# Schematic_WMR.net
KiCad netlist of a schematic drawn in Altium Designer
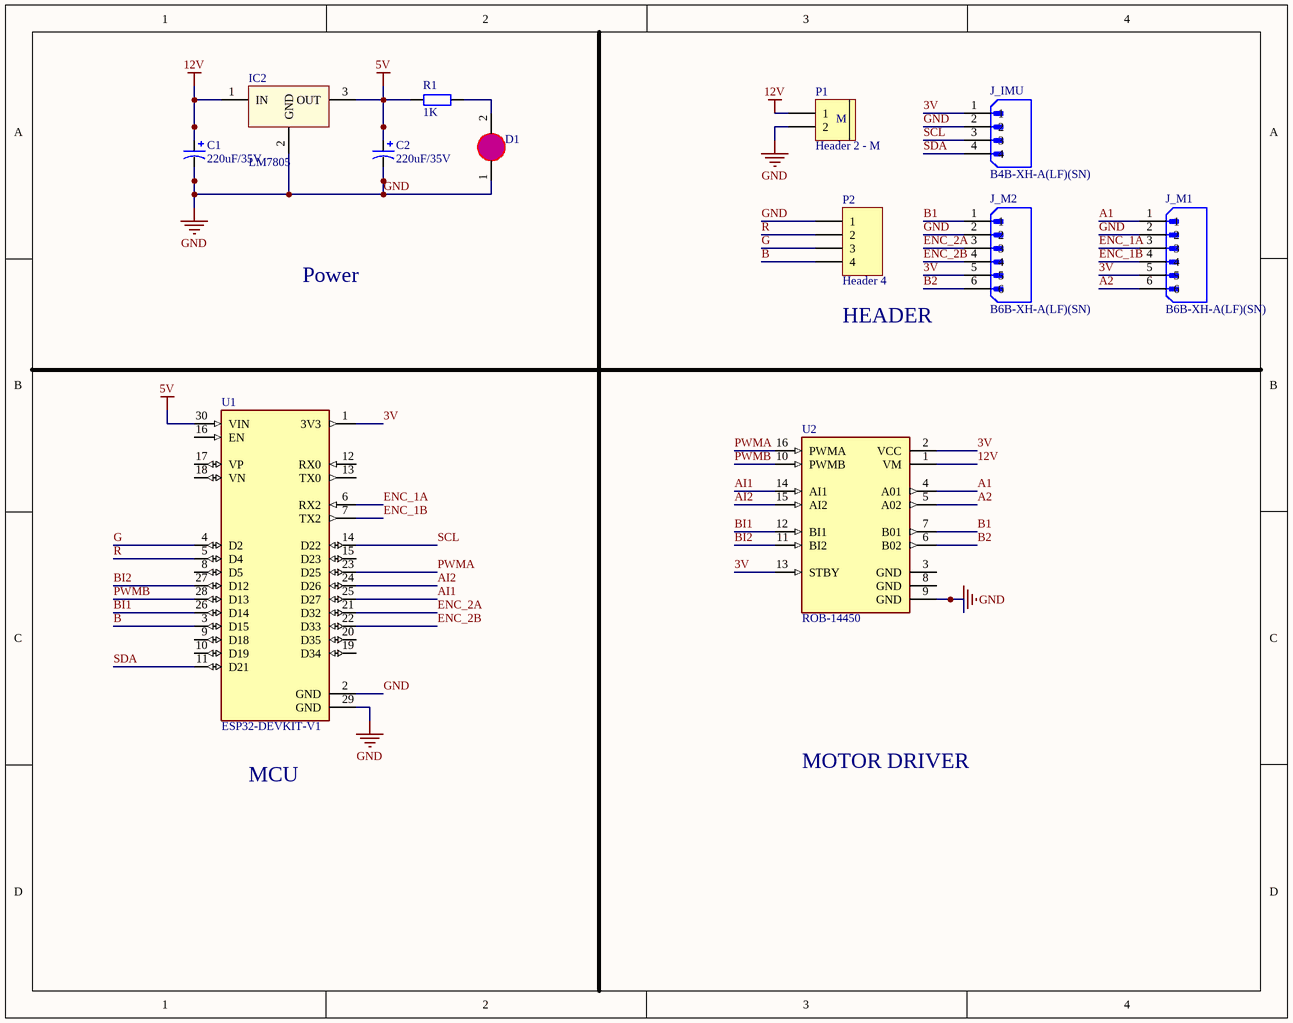
[diagram p0: Schematic_WMR.SchDoc]

(export (version "E")
  (design (tool "Eeschema 10.0.6"))
  (components
    (comp (ref "C1")
      (value "220uF/35V")
      (footprint "CAP_ALUM_SMD_80102_TYPE_F")
      (description "CAP ALUM 220uF 20% 35V SMD")
      (fields (field (name "MPN") "EEE-FK1V221P") (field (name "MFR") "Panasonic"))
      (libsource (lib "BYTECH_HW_LIB_2019 (1)") (part "EEE-FK1V221P"))
    )
    (comp (ref "C2")
      (value "220uF/35V")
      (footprint "CAP_ALUM_SMD_80102_TYPE_F")
      (description "CAP ALUM 220uF 20% 35V SMD")
      (fields (field (name "MPN") "EEE-FK1V221P") (field (name "MFR") "Panasonic"))
      (libsource (lib "BYTECH_HW_LIB_2019 (1)") (part "EEE-FK1V221P"))
    )
    (comp (ref "D1")
      (value "LED3")
      (footprint "LED0805")
      (description "LED SMD 0805")
      (libsource (lib "My Library") (part "LED0805"))
    )
    (comp (ref "IC2")
      (value "LM7805")
      (footprint "QTO-220")
      (description "On ap +, from + 5 to + 24VDC")
      (libsource (lib "My Library") (part "LM78xx"))
    )
    (comp (ref "J_IMU")
      (value "B4B-XH-A(LF)(SN)")
      (footprint "JST_B4B-XH-A(LF)(SN)")
      (description "Connector Header Through Hole 4 position 0.098 (2.50mm)")
      (fields (field (name "MF") "JST Sales"))
      (libsource (lib "B4B-XH-A_LF__SN_") (part "B4B-XH-A(LF)(SN)"))
    )
    (comp (ref "J_M1")
      (value "B6B-XH-A(LF)(SN)")
      (footprint "JST_B6B-XH-A(LF)(SN)")
      (description "Connector Header Through Hole 6 position 0.098 (2.50mm)")
      (fields (field (name "MF") "JST Sales"))
      (libsource (lib "B6B-XH-A_LF__SN_") (part "B6B-XH-A(LF)(SN)"))
    )
    (comp (ref "J_M2")
      (value "B6B-XH-A(LF)(SN)")
      (footprint "JST_B6B-XH-A(LF)(SN)")
      (description "Connector Header Through Hole 6 position 0.098 (2.50mm)")
      (fields (field (name "MF") "JST Sales"))
      (libsource (lib "B6B-XH-A_LF__SN_") (part "B6B-XH-A(LF)(SN)"))
    )
    (comp (ref "P1")
      (value "Header 2 - M")
      (footprint "Medium - Header 2")
      (description "Header, 2-Pin, Medium")
      (fields (field (name "PUBLISHER") "Altium Limited"))
      (libsource (lib "BYTECH_HW_LIB_2019 (1)") (part "Header 2 - M"))
    )
    (comp (ref "P2")
      (value "Header 4")
      (footprint "HDR1X4")
      (description "Header, 4-Pin")
      (fields (field (name "PUBLISHER") "Altium Limited"))
      (libsource (lib "My Library") (part "Header 4"))
    )
    (comp (ref "R1")
      (value "1K")
      (footprint "SM-0805")
      (description "Resistor SMD")
      (libsource (lib "My Library") (part "RM"))
    )
    (comp (ref "U1")
      (value "ESP32-DEVKIT-V1")
      (footprint "MODULE_ESP32_DEVKIT_V1")
      (fields (field (name "MF") "Do it"))
      (libsource (lib "ESP32-DEVKIT-V1") (part "ESP32-DEVKIT-V1"))
    )
    (comp (ref "U2")
      (value "ROB-14450")
      (footprint "MODULE_ROB-14450")
      (description "TB6612FNG Motor Controller/Driver Power Management Evaluation Board")
      (fields (field (name "MF") "SparkFun Electronics"))
      (libsource (lib "ROB-14450") (part "ROB-14450"))
    )
  )
  (nets
    (net (code "1") (name "/3V") (class "Default")
      (node (ref "J_IMU") (pin "1") (pinfunction "1_1") (pintype "passive"))
      (node (ref "J_M1") (pin "5") (pinfunction "5_5") (pintype "passive"))
      (node (ref "J_M2") (pin "5") (pinfunction "5_5") (pintype "passive"))
      (node (ref "U1") (pin "1") (pinfunction "3V3_1") (pintype "output"))
      (node (ref "U2") (pin "13") (pinfunction "STBY_13") (pintype "input"))
      (node (ref "U2") (pin "2") (pinfunction "VCC_2") (pintype "power_in"))
    )
    (net (code "2") (name "/A1") (class "Default")
      (node (ref "J_M1") (pin "1") (pinfunction "1_1") (pintype "passive"))
      (node (ref "U2") (pin "4") (pinfunction "A01_4") (pintype "output"))
    )
    (net (code "3") (name "/A2") (class "Default")
      (node (ref "J_M1") (pin "6") (pinfunction "6_6") (pintype "passive"))
      (node (ref "U2") (pin "5") (pinfunction "A02_5") (pintype "output"))
    )
    (net (code "4") (name "/AI1") (class "Default")
      (node (ref "U1") (pin "25") (pinfunction "D27_25") (pintype "bidirectional"))
      (node (ref "U2") (pin "14") (pinfunction "AI1_14") (pintype "input"))
    )
    (net (code "5") (name "/AI2") (class "Default")
      (node (ref "U1") (pin "24") (pinfunction "D26_24") (pintype "bidirectional"))
      (node (ref "U2") (pin "15") (pinfunction "AI2_15") (pintype "input"))
    )
    (net (code "6") (name "/B") (class "Default")
      (node (ref "P2") (pin "4") (pinfunction "4_4") (pintype "passive"))
      (node (ref "U1") (pin "3") (pinfunction "D15_3") (pintype "bidirectional"))
    )
    (net (code "7") (name "/B1") (class "Default")
      (node (ref "J_M2") (pin "1") (pinfunction "1_1") (pintype "passive"))
      (node (ref "U2") (pin "7") (pinfunction "B01_7") (pintype "output"))
    )
    (net (code "8") (name "/B2") (class "Default")
      (node (ref "J_M2") (pin "6") (pinfunction "6_6") (pintype "passive"))
      (node (ref "U2") (pin "6") (pinfunction "B02_6") (pintype "output"))
    )
    (net (code "9") (name "/BI1") (class "Default")
      (node (ref "U1") (pin "26") (pinfunction "D14_26") (pintype "bidirectional"))
      (node (ref "U2") (pin "12") (pinfunction "BI1_12") (pintype "input"))
    )
    (net (code "10") (name "/BI2") (class "Default")
      (node (ref "U1") (pin "27") (pinfunction "D12_27") (pintype "bidirectional"))
      (node (ref "U2") (pin "11") (pinfunction "BI2_11") (pintype "input"))
    )
    (net (code "11") (name "/ENC_1A") (class "Default")
      (node (ref "J_M1") (pin "3") (pinfunction "3_3") (pintype "passive"))
      (node (ref "U1") (pin "6") (pinfunction "RX2_6") (pintype "input"))
    )
    (net (code "12") (name "/ENC_1B") (class "Default")
      (node (ref "J_M1") (pin "4") (pinfunction "4_4") (pintype "passive"))
      (node (ref "U1") (pin "7") (pinfunction "TX2_7") (pintype "output"))
    )
    (net (code "13") (name "/ENC_2A") (class "Default")
      (node (ref "J_M2") (pin "3") (pinfunction "3_3") (pintype "passive"))
      (node (ref "U1") (pin "21") (pinfunction "D32_21") (pintype "bidirectional"))
    )
    (net (code "14") (name "/ENC_2B") (class "Default")
      (node (ref "J_M2") (pin "4") (pinfunction "4_4") (pintype "passive"))
      (node (ref "U1") (pin "22") (pinfunction "D33_22") (pintype "bidirectional"))
    )
    (net (code "15") (name "/G") (class "Default")
      (node (ref "P2") (pin "3") (pinfunction "3_3") (pintype "passive"))
      (node (ref "U1") (pin "4") (pinfunction "D2_4") (pintype "bidirectional"))
    )
    (net (code "16") (name "/PWMA") (class "Default")
      (node (ref "U1") (pin "23") (pinfunction "D25_23") (pintype "bidirectional"))
      (node (ref "U2") (pin "16") (pinfunction "PWMA_16") (pintype "input"))
    )
    (net (code "17") (name "/PWMB") (class "Default")
      (node (ref "U1") (pin "28") (pinfunction "D13_28") (pintype "bidirectional"))
      (node (ref "U2") (pin "10") (pinfunction "PWMB_10") (pintype "input"))
    )
    (net (code "18") (name "/R") (class "Default")
      (node (ref "P2") (pin "2") (pinfunction "2_2") (pintype "passive"))
      (node (ref "U1") (pin "5") (pinfunction "D4_5") (pintype "bidirectional"))
    )
    (net (code "19") (name "/SCL") (class "Default")
      (node (ref "J_IMU") (pin "3") (pinfunction "3_3") (pintype "passive"))
      (node (ref "U1") (pin "14") (pinfunction "D22_14") (pintype "bidirectional"))
    )
    (net (code "20") (name "/SDA") (class "Default")
      (node (ref "J_IMU") (pin "4") (pinfunction "4_4") (pintype "passive"))
      (node (ref "U1") (pin "11") (pinfunction "D21_11") (pintype "bidirectional"))
    )
    (net (code "21") (name "5V") (class "Default")
      (node (ref "C2") (pin "1") (pinfunction "1_1") (pintype "passive"))
      (node (ref "IC2") (pin "3") (pinfunction "OUT_3") (pintype "passive"))
      (node (ref "R1") (pin "1") (pinfunction "1_1") (pintype "passive"))
      (node (ref "U1") (pin "30") (pinfunction "VIN_30") (pintype "input"))
    )
    (net (code "22") (name "12V") (class "Default")
      (node (ref "C1") (pin "1") (pinfunction "1_1") (pintype "passive"))
      (node (ref "IC2") (pin "1") (pinfunction "IN_1") (pintype "passive"))
      (node (ref "P1") (pin "1") (pinfunction "1_1") (pintype "passive"))
      (node (ref "U2") (pin "1") (pinfunction "VM_1") (pintype "power_in"))
    )
    (net (code "23") (name "GND") (class "Default")
      (node (ref "C1") (pin "2") (pinfunction "2_2") (pintype "passive"))
      (node (ref "C2") (pin "2") (pinfunction "2_2") (pintype "passive"))
      (node (ref "D1") (pin "1") (pinfunction "A_1") (pintype "passive"))
      (node (ref "IC2") (pin "2") (pinfunction "GND_2") (pintype "passive"))
      (node (ref "J_IMU") (pin "2") (pinfunction "2_2") (pintype "passive"))
      (node (ref "J_M1") (pin "2") (pinfunction "2_2") (pintype "passive"))
      (node (ref "J_M2") (pin "2") (pinfunction "2_2") (pintype "passive"))
      (node (ref "P1") (pin "2") (pinfunction "2_2") (pintype "passive"))
      (node (ref "P2") (pin "1") (pinfunction "1_1") (pintype "passive"))
      (node (ref "U1") (pin "2") (pinfunction "GND_2") (pintype "power_in"))
      (node (ref "U1") (pin "29") (pinfunction "GND_29") (pintype "power_in"))
      (node (ref "U2") (pin "9") (pinfunction "GND_9") (pintype "power_in"))
    )
    (net (code "24") (name "Net-(D1-K)") (class "Default")
      (node (ref "D1") (pin "2") (pinfunction "K_2") (pintype "passive"))
      (node (ref "R1") (pin "2") (pinfunction "2_2") (pintype "passive"))
    )
    (net (code "25") (name "unconnected-(U1-D5-Pad8)") (class "Default")
      (node (ref "U1") (pin "8") (pinfunction "D5_8") (pintype "bidirectional"))
    )
    (net (code "26") (name "unconnected-(U1-D18-Pad9)") (class "Default")
      (node (ref "U1") (pin "9") (pinfunction "D18_9") (pintype "bidirectional"))
    )
    (net (code "27") (name "unconnected-(U1-D19-Pad10)") (class "Default")
      (node (ref "U1") (pin "10") (pinfunction "D19_10") (pintype "bidirectional"))
    )
    (net (code "28") (name "unconnected-(U1-D23-Pad15)") (class "Default")
      (node (ref "U1") (pin "15") (pinfunction "D23_15") (pintype "bidirectional"))
    )
    (net (code "29") (name "unconnected-(U1-D34-Pad19)") (class "Default")
      (node (ref "U1") (pin "19") (pinfunction "D34_19") (pintype "bidirectional"))
    )
    (net (code "30") (name "unconnected-(U1-D35-Pad20)") (class "Default")
      (node (ref "U1") (pin "20") (pinfunction "D35_20") (pintype "bidirectional"))
    )
    (net (code "31") (name "unconnected-(U1-EN-Pad16)") (class "Default")
      (node (ref "U1") (pin "16") (pinfunction "EN_16") (pintype "input"))
    )
    (net (code "32") (name "unconnected-(U1-RX0-Pad12)") (class "Default")
      (node (ref "U1") (pin "12") (pinfunction "RX0_12") (pintype "input"))
    )
    (net (code "33") (name "unconnected-(U1-TX0-Pad13)") (class "Default")
      (node (ref "U1") (pin "13") (pinfunction "TX0_13") (pintype "output"))
    )
    (net (code "34") (name "unconnected-(U1-VN-Pad18)") (class "Default")
      (node (ref "U1") (pin "18") (pinfunction "VN_18") (pintype "bidirectional"))
    )
    (net (code "35") (name "unconnected-(U1-VP-Pad17)") (class "Default")
      (node (ref "U1") (pin "17") (pinfunction "VP_17") (pintype "bidirectional"))
    )
    (net (code "36") (name "unconnected-(U2-GND-Pad3)") (class "Default")
      (node (ref "U2") (pin "3") (pinfunction "GND_3") (pintype "power_in"))
    )
    (net (code "37") (name "unconnected-(U2-GND-Pad8)") (class "Default")
      (node (ref "U2") (pin "8") (pinfunction "GND_8") (pintype "power_in"))
    )
  )
)
